# UARTRecoder.net
KiCad netlist of a schematic drawn in Altium Designer
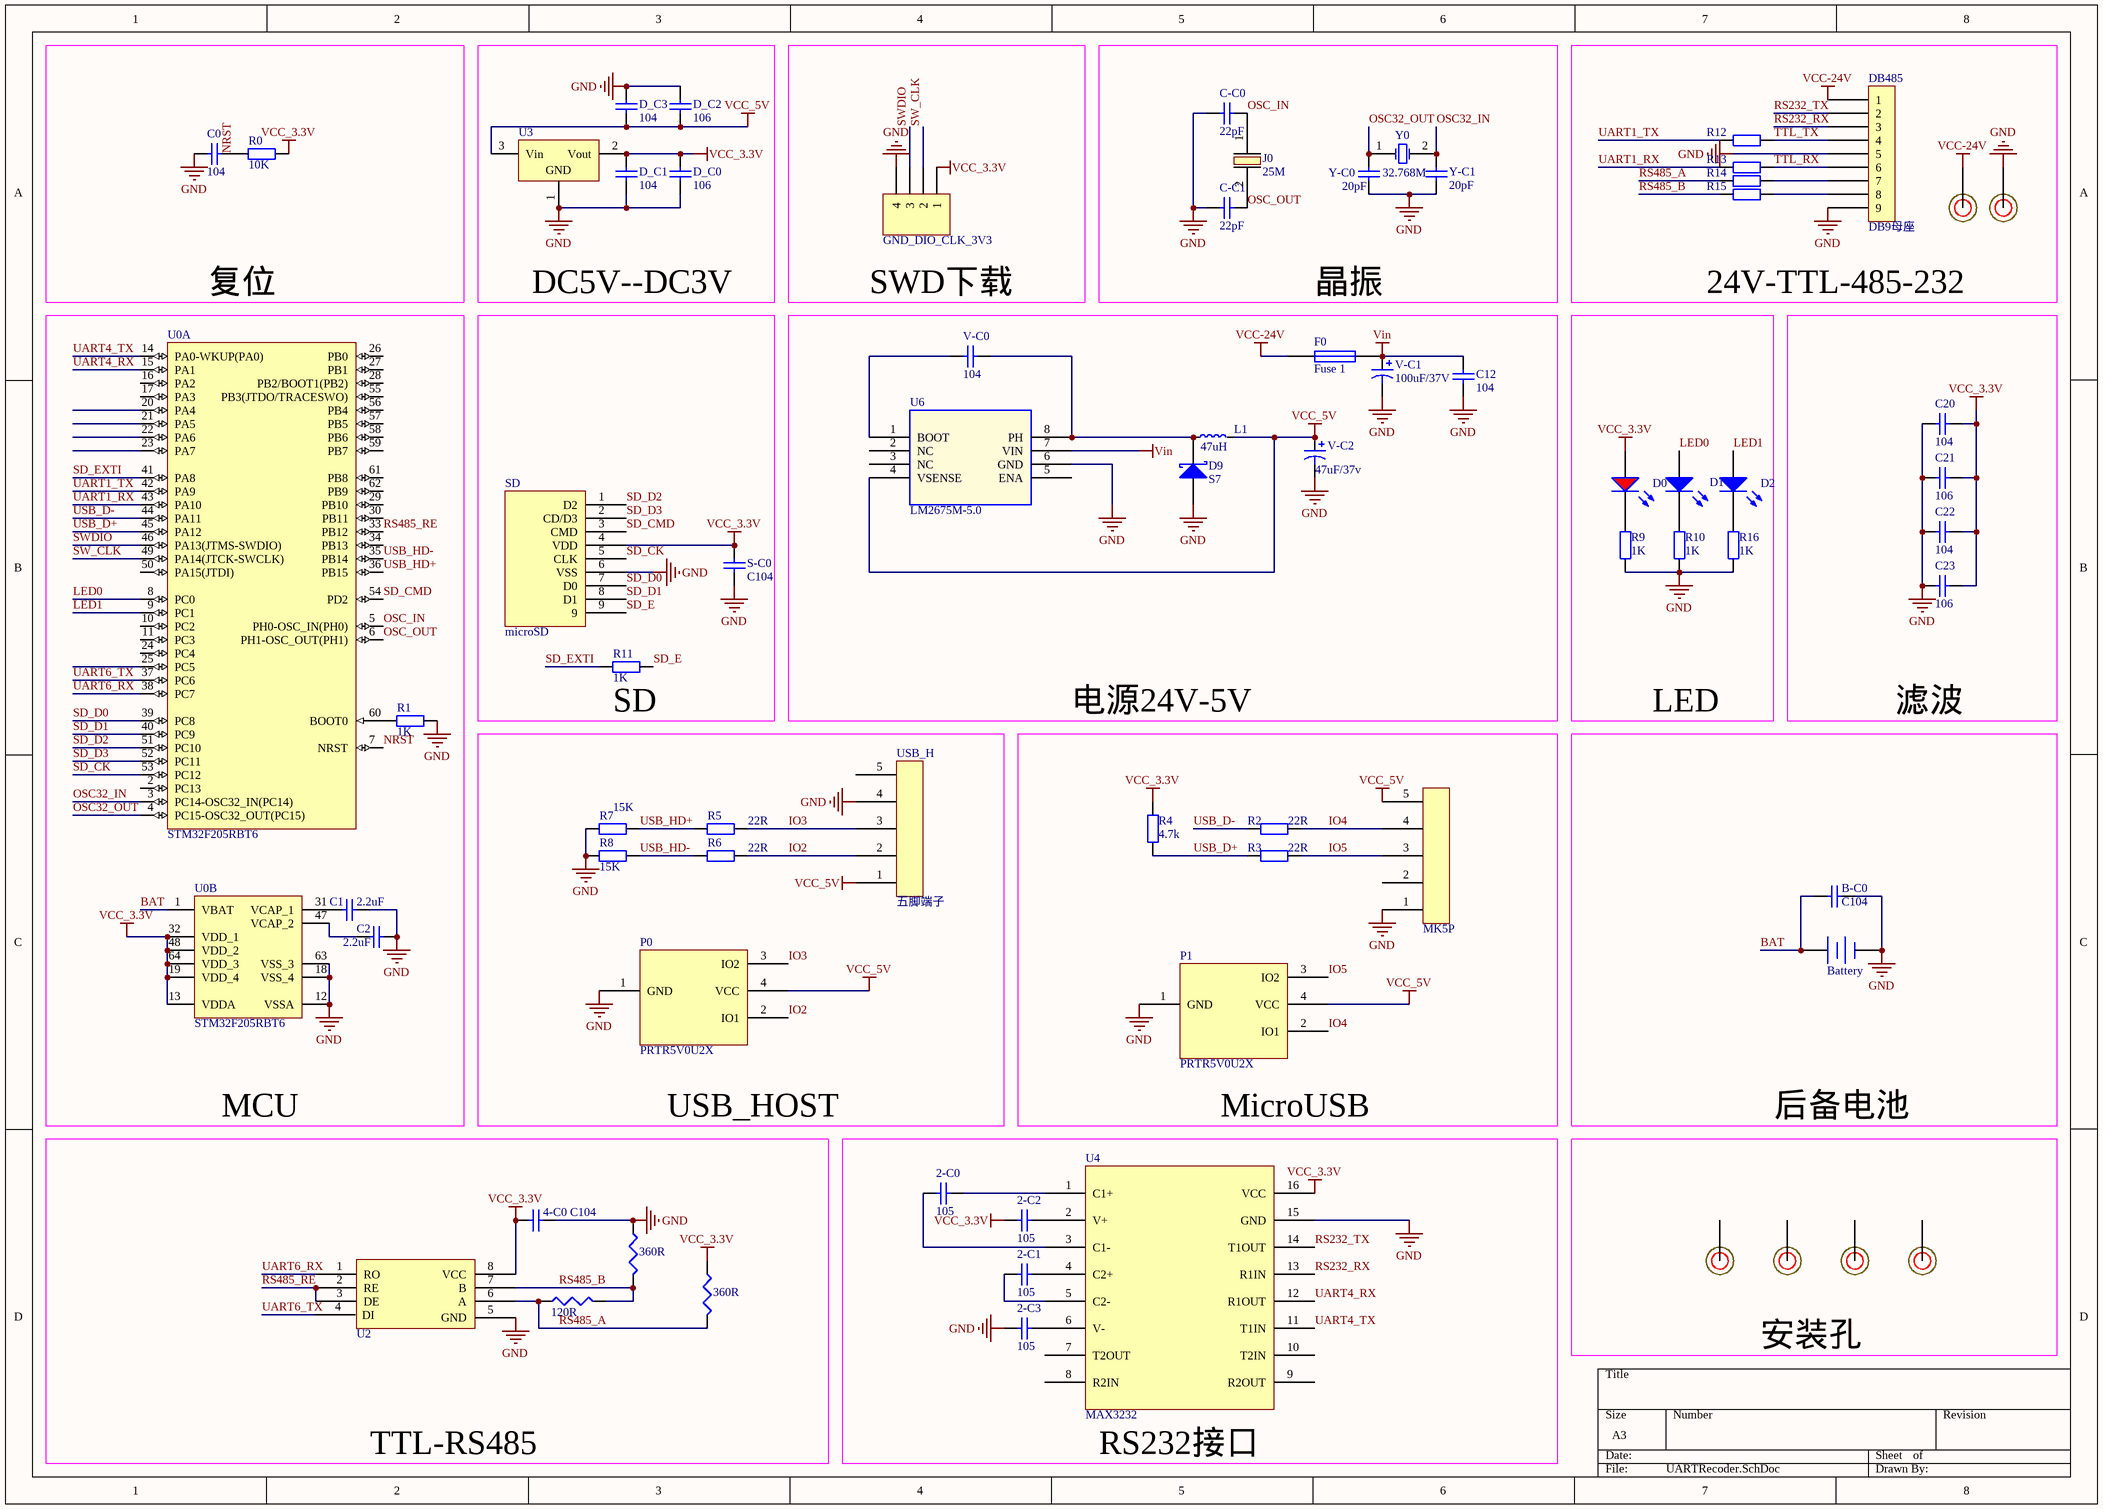
[diagram p0: UARTRecoder.SchDoc]

(export (version "E")
  (design (tool "Eeschema 10.0.6"))
  (components
    (comp (ref "2-C0")
      (value "105")
      (footprint "C-RAD-0805")
      (description "贴片电容")
      (libsource (lib "JiaLiChuang") (part "0805 1uF (105) 10% 50V"))
    )
    (comp (ref "2-C1")
      (value "105")
      (footprint "C-RAD-0805")
      (description "贴片电容")
      (libsource (lib "JiaLiChuang") (part "0805 1uF (105) 10% 50V"))
    )
    (comp (ref "2-C2")
      (value "105")
      (footprint "C-RAD-0805")
      (description "贴片电容")
      (libsource (lib "JiaLiChuang") (part "0805 1uF (105) 10% 50V"))
    )
    (comp (ref "2-C3")
      (value "105")
      (footprint "C-RAD-0805")
      (description "贴片电容")
      (libsource (lib "JiaLiChuang") (part "0805 1uF (105) 10% 50V"))
    )
    (comp (ref "4-C0")
      (value "C104")
      (footprint "C-RAD-0805")
      (description "Capacitor (Semiconductor SIM Model)")
      (fields (field (name "PUBLISHER") "Altium Limited"))
      (libsource (lib "Miscellaneous Devices") (part "Cap Semi"))
    )
    (comp (ref "4-R0")
      (value "360R")
      (footprint "R2012-0805")
      (description "Resistor")
      (fields (field (name "Comment") "R360"))
      (libsource (lib "Miscellaneous Devices") (part "Res3"))
    )
    (comp (ref "4-R1")
      (value "360R")
      (footprint "R2012-0805")
      (description "Resistor")
      (fields (field (name "Comment") "R360"))
      (libsource (lib "Miscellaneous Devices") (part "Res3"))
    )
    (comp (ref "4-R2")
      (value "120R")
      (footprint "R2012-0805")
      (description "Resistor")
      (fields (field (name "Comment") "R120"))
      (libsource (lib "Miscellaneous Devices") (part "Res3"))
    )
    (comp (ref "24V") (value "1孔") (footprint "HOLEx1") (libsource (lib "我的库") (part "1孔")))
    (comp (ref "B-C0")
      (value "C104")
      (footprint "C-RAD-0805")
      (description "Capacitor (Semiconductor SIM Model)")
      (fields (field (name "PUBLISHER") "Altium Limited"))
      (libsource (lib "Miscellaneous Devices") (part "Cap Semi"))
    )
    (comp (ref "bat")
      (value "Battery")
      (footprint "BATM")
      (description "Multicell Battery")
      (fields (field (name "PUBLISHER") "Altium Limited"))
      (libsource (lib "Devices") (part "Battery"))
    )
    (comp (ref "C-C0")
      (value "22pF")
      (footprint "C-RAD-0805")
      (description "贴片电容")
      (libsource (lib "Miscellaneous Devices LC") (part "0603 22pF (220) 5% 50V"))
    )
    (comp (ref "C-C1")
      (value "22pF")
      (footprint "C-RAD-0805")
      (description "贴片电容")
      (libsource (lib "Miscellaneous Devices LC") (part "0603 22pF (220) 5% 50V"))
    )
    (comp (ref "C0")
      (value "104")
      (footprint "C-RAD-0805")
      (description "贴片电容")
      (libsource (lib "JiaLiChuang") (part "0805 100nF(104) 10% 50V"))
    )
    (comp (ref "C1")
      (value "2.2uF")
      (footprint "C-RAD-0805")
      (description "贴片电容")
      (libsource (lib "JiaLiChuang") (part "0805 2.2uF (225) 20% 50V"))
    )
    (comp (ref "C2")
      (value "2.2uF")
      (footprint "C-RAD-0805")
      (description "贴片电容")
      (libsource (lib "JiaLiChuang") (part "0805 2.2uF (225) 20% 50V"))
    )
    (comp (ref "C12")
      (value "104")
      (footprint "C-RAD-0805")
      (description "Capacitor")
      (fields (field (name "PUBLISHER") "Altium Limited"))
      (libsource (lib "*") (part "Cap"))
    )
    (comp (ref "C20")
      (value "104")
      (footprint "C-RAD-0805")
      (description "Capacitor")
      (fields (field (name "PUBLISHER") "Altium Limited"))
      (libsource (lib "*") (part "Cap"))
    )
    (comp (ref "C21")
      (value "106")
      (footprint "C-RAD-0805")
      (description "Capacitor")
      (fields (field (name "PUBLISHER") "Altium Limited"))
      (libsource (lib "*") (part "Cap"))
    )
    (comp (ref "C22")
      (value "104")
      (footprint "C-RAD-0805")
      (description "Capacitor")
      (fields (field (name "PUBLISHER") "Altium Limited"))
      (libsource (lib "*") (part "Cap"))
    )
    (comp (ref "C23")
      (value "106")
      (footprint "C-RAD-0805")
      (description "Capacitor")
      (fields (field (name "PUBLISHER") "Altium Limited"))
      (libsource (lib "*") (part "Cap"))
    )
    (comp (ref "D0")
      (value "Rled")
      (footprint "0805_LED_S1")
      (description "发光二极管")
      (libsource (lib "JiaLiChuang") (part "0805 红灯"))
    )
    (comp (ref "D1")
      (value "Bled")
      (footprint "0805_LED_S1")
      (description "发光二极管")
      (libsource (lib "JiaLiChuang") (part "0805 蓝灯"))
    )
    (comp (ref "D2")
      (value "Bled")
      (footprint "0805_LED_S1")
      (description "发光二极管")
      (libsource (lib "JiaLiChuang") (part "0805 蓝灯"))
    )
    (comp (ref "D9")
      (value "S7")
      (footprint "SOD123")
      (description "Schottky Diode")
      (fields (field (name "PUBLISHER") "Altium Limited"))
      (libsource (lib "*") (part "D Schottky"))
    )
    (comp (ref "DB485") (value "DB9母座") (footprint "DB9-F") (libsource (lib "我的库") (part "9脚封装DB9")))
    (comp (ref "D_C0")
      (value "106")
      (footprint "C-RAD-0805")
      (description "贴片电容")
      (libsource (lib "JiaLiChuang") (part "0805 100nF(104) 10% 50V"))
    )
    (comp (ref "D_C1")
      (value "104")
      (footprint "C-RAD-0805")
      (description "贴片电容")
      (libsource (lib "JiaLiChuang") (part "0805 100nF(104) 10% 50V"))
    )
    (comp (ref "D_C2")
      (value "106")
      (footprint "C-RAD-0805")
      (description "贴片电容")
      (libsource (lib "JiaLiChuang") (part "0805 100nF(104) 10% 50V"))
    )
    (comp (ref "D_C3")
      (value "104")
      (footprint "C-RAD-0805")
      (description "贴片电容")
      (libsource (lib "JiaLiChuang") (part "0805 100nF(104) 10% 50V"))
    )
    (comp (ref "EGND0") (value "1孔") (footprint "HOLEx1") (libsource (lib "我的库") (part "1孔")))
    (comp (ref "EGND1") (value "1孔") (footprint "HOLEx1") (libsource (lib "我的库") (part "1孔")))
    (comp (ref "EGND2") (value "1孔") (footprint "HOLEx1") (libsource (lib "我的库") (part "1孔")))
    (comp (ref "EGND3") (value "1孔") (footprint "HOLEx1") (libsource (lib "我的库") (part "1孔")))
    (comp (ref "F0")
      (value "Fuse 1")
      (footprint "1812")
      (description "Fuse")
      (fields (field (name "PUBLISHER") "Altium Limited"))
      (libsource (lib "Devices") (part "Fuse 1"))
    )
    (comp (ref "GND") (value "1孔") (footprint "HOLEx1") (libsource (lib "我的库") (part "1孔")))
    (comp (ref "GND_DIO_CLK_3V3")
      (value "Header 4")
      (footprint "HDR1X4")
      (description "Header, 4-Pin")
      (fields (field (name "PUBLISHER") "Altium Limited"))
      (libsource (lib "Connectors") (part "Header 4"))
    )
    (comp (ref "J0") (value "25M") (footprint "晶振HC-49S") (libsource (lib "MyADLib") (part "晶振")))
    (comp (ref "L1") (value "47uH") (footprint "L-SMD-7") (libsource (lib "*") (part "Lnductor")))
    (comp (ref "MK5P") (value "五脚端子") (footprint "USB-MICRO1") (libsource (lib "我的库") (part "五脚端子")))
    (comp (ref "P0") (value "PRTR5V0U2X") (footprint "SOT-143") (libsource (lib "我的库") (part "PRTR5V0U2X")))
    (comp (ref "P1") (value "PRTR5V0U2X") (footprint "SOT-143") (libsource (lib "我的库") (part "PRTR5V0U2X")))
    (comp (ref "R0")
      (value "10K")
      (footprint "R2012-0805")
      (description "贴片电阻")
      (libsource (lib "JiaLiChuang") (part "0805 1KΩ (1001) 1%"))
    )
    (comp (ref "R1")
      (value "1K")
      (footprint "R2012-0805")
      (description "贴片电阻")
      (libsource (lib "JiaLiChuang") (part "0603 1KΩ (1001) 1%"))
    )
    (comp (ref "R2")
      (value "22R")
      (footprint "R2012-0805")
      (description "贴片电阻")
      (libsource (lib "") (part "0805 1KΩ (1001) 1%_2"))
    )
    (comp (ref "R3")
      (value "22R")
      (footprint "R2012-0805")
      (description "贴片电阻")
      (libsource (lib "") (part "0805 1KΩ (1001) 1%_2"))
    )
    (comp (ref "R4")
      (value "4.7k")
      (footprint "R2012-0805")
      (description "贴片电阻")
      (libsource (lib "") (part "0805 1KΩ (1001) 1%_1"))
    )
    (comp (ref "R5")
      (value "22R")
      (footprint "R2012-0805")
      (description "贴片电阻")
      (libsource (lib "") (part "0805 1KΩ (1001) 1%_2"))
    )
    (comp (ref "R6")
      (value "22R")
      (footprint "R2012-0805")
      (description "贴片电阻")
      (libsource (lib "") (part "0805 1KΩ (1001) 1%_2"))
    )
    (comp (ref "R7")
      (value "15K")
      (footprint "R2012-0805")
      (description "贴片电阻")
      (libsource (lib "JiaLiChuang") (part "0805 1KΩ (1001) 1%"))
    )
    (comp (ref "R8")
      (value "15K")
      (footprint "R2012-0805")
      (description "贴片电阻")
      (libsource (lib "JiaLiChuang") (part "0805 1KΩ (1001) 1%"))
    )
    (comp (ref "R9")
      (value "1K")
      (footprint "R2012-0805")
      (description "贴片电阻")
      (libsource (lib "") (part "0805 1KΩ (1001) 1%_1"))
    )
    (comp (ref "R10")
      (value "1K")
      (footprint "R2012-0805")
      (description "贴片电阻")
      (libsource (lib "") (part "0805 1KΩ (1001) 1%_1"))
    )
    (comp (ref "R11")
      (value "1K")
      (footprint "R2012-0805")
      (description "贴片电阻")
      (libsource (lib "JiaLiChuang") (part "0603 1KΩ (1001) 1%"))
    )
    (comp (ref "R12")
      (value "1K")
      (footprint "R2012-0805")
      (description "贴片电阻")
      (libsource (lib "JiaLiChuang") (part "0805 1KΩ (1001) 1%"))
    )
    (comp (ref "R13")
      (value "1K")
      (footprint "R2012-0805")
      (description "贴片电阻")
      (libsource (lib "JiaLiChuang") (part "0805 1KΩ (1001) 1%"))
    )
    (comp (ref "R14")
      (value "1K")
      (footprint "R2012-0805")
      (description "贴片电阻")
      (libsource (lib "JiaLiChuang") (part "0805 1KΩ (1001) 1%"))
    )
    (comp (ref "R15")
      (value "1K")
      (footprint "R2012-0805")
      (description "贴片电阻")
      (libsource (lib "JiaLiChuang") (part "0805 1KΩ (1001) 1%"))
    )
    (comp (ref "R16")
      (value "1K")
      (footprint "R2012-0805")
      (description "贴片电阻")
      (libsource (lib "") (part "0805 1KΩ (1001) 1%_1"))
    )
    (comp (ref "S-C0")
      (value "C104")
      (footprint "C-RAD-0805")
      (description "Capacitor (Semiconductor SIM Model)")
      (fields (field (name "PUBLISHER") "Altium Limited"))
      (libsource (lib "Miscellaneous Devices") (part "Cap Semi"))
    )
    (comp (ref "SD") (value "microSD") (footprint "SDCARD_B") (libsource (lib "我的库") (part "microSD")))
    (comp (ref "U0")
      (value "STM32F205RBT6")
      (footprint "LQFP-64")
      (libsource (lib "STM32F2") (part "STM32F205RBT6"))
    )
    (comp (ref "U2") (value "485") (footprint "SOP8") (libsource (lib "我的库") (part "SP3485")))
    (comp (ref "U3")
      (value "AMS1117-3.3")
      (footprint "SOT-223")
      (description "低压差线性稳压(LDO)")
      (libsource (lib "JiaLiChuang") (part "SOT-223 AMS1117-3.3"))
    )
    (comp (ref "U4") (value "MAX3232") (footprint "SOP-16") (libsource (lib "我的库") (part "MAX3232")))
    (comp (ref "U6")
      (value "LM2675M-5.0")
      (footprint "SOP8 - 3d")
      (libsource (lib "Schlib1") (part "TPS5410"))
    )
    (comp (ref "USB_H") (value "五脚端子") (footprint "USB") (libsource (lib "MyADLib") (part "五脚端子")))
    (comp (ref "V-C0")
      (value "104")
      (footprint "C-RAD-0805")
      (description "贴片电容")
      (libsource (lib "JiaLiChuang") (part "0805 100nF(104) 10% 50V"))
    )
    (comp (ref "V-C1")
      (value "100uF/37V")
      (footprint "SMD-EC-F6.3")
      (description "Polarized Capacitor (Surface Mount)")
      (fields (field (name "PUBLISHER") "Altium Limited"))
      (libsource (lib "Miscellaneous Devices") (part "Cap Pol3"))
    )
    (comp (ref "V-C2")
      (value "47uF/37v")
      (footprint "SMD-EC-F4")
      (description "Polarized Capacitor (Surface Mount)")
      (fields (field (name "PUBLISHER") "Altium Limited"))
      (libsource (lib "Miscellaneous Devices") (part "Cap Pol3"))
    )
    (comp (ref "Y-C0")
      (value "20pF")
      (footprint "C-RAD-0805")
      (description "贴片电容")
      (libsource (lib "Miscellaneous Devices LC") (part "0805 20pF (200) 5% 50V"))
    )
    (comp (ref "Y-C1")
      (value "20pF")
      (footprint "C-RAD-0805")
      (description "贴片电容")
      (libsource (lib "Miscellaneous Devices LC") (part "0805 20pF (200) 5% 50V"))
    )
    (comp (ref "Y0")
      (value "32.768M")
      (footprint "XTAL32")
      (description "Crystal Oscillator")
      (fields (field (name "PUBLISHER") "Altium Limited"))
      (libsource (lib "Miscellaneous Devices") (part "XTAL"))
    )
  )
  (nets
    (net (code "1") (name "/BAT") (class "Default")
      (node (ref "B-C0") (pin "2") (pinfunction "2_2") (pintype "passive"))
      (node (ref "U0") (pin "1") (pinfunction "VBAT_1") (pintype "power_in"))
      (node (ref "bat") (pin "1") (pinfunction "+_1") (pintype "passive"))
    )
    (net (code "2") (name "/IO2") (class "Default")
      (node (ref "P0") (pin "2") (pinfunction "IO1_2") (pintype "passive"))
      (node (ref "R6") (pin "2") (pinfunction "2_2") (pintype "passive"))
      (node (ref "USB_H") (pin "2") (pinfunction "2_2") (pintype "passive"))
    )
    (net (code "3") (name "/IO3") (class "Default")
      (node (ref "P0") (pin "3") (pinfunction "IO2_3") (pintype "passive"))
      (node (ref "R5") (pin "2") (pinfunction "2_2") (pintype "passive"))
      (node (ref "USB_H") (pin "3") (pinfunction "3_3") (pintype "passive"))
    )
    (net (code "4") (name "/IO4") (class "Default")
      (node (ref "MK5P") (pin "4") (pinfunction "4_4") (pintype "passive"))
      (node (ref "P1") (pin "2") (pinfunction "IO1_2") (pintype "passive"))
      (node (ref "R2") (pin "2") (pinfunction "2_2") (pintype "passive"))
    )
    (net (code "5") (name "/IO5") (class "Default")
      (node (ref "MK5P") (pin "3") (pinfunction "3_3") (pintype "passive"))
      (node (ref "P1") (pin "3") (pinfunction "IO2_3") (pintype "passive"))
      (node (ref "R3") (pin "2") (pinfunction "2_2") (pintype "passive"))
    )
    (net (code "6") (name "/LED0") (class "Default")
      (node (ref "D1") (pin "A") (pinfunction "A_A") (pintype "passive"))
      (node (ref "U0") (pin "8") (pinfunction "PC0_8") (pintype "bidirectional"))
    )
    (net (code "7") (name "/LED1") (class "Default")
      (node (ref "D2") (pin "A") (pinfunction "A_A") (pintype "passive"))
      (node (ref "U0") (pin "9") (pinfunction "PC1_9") (pintype "bidirectional"))
    )
    (net (code "8") (name "/NRST") (class "Default")
      (node (ref "C0") (pin "1") (pinfunction "1_1") (pintype "passive"))
      (node (ref "R0") (pin "2") (pinfunction "2_2") (pintype "passive"))
      (node (ref "U0") (pin "7") (pinfunction "NRST_7") (pintype "bidirectional"))
    )
    (net (code "9") (name "/OSC32_IN") (class "Default")
      (node (ref "U0") (pin "3") (pinfunction "PC14-OSC32_IN(PC14)_3") (pintype "bidirectional"))
      (node (ref "Y-C1") (pin "2") (pinfunction "2_2") (pintype "passive"))
      (node (ref "Y0") (pin "2") (pinfunction "OSC2_2") (pintype "passive"))
    )
    (net (code "10") (name "/OSC32_OUT") (class "Default")
      (node (ref "U0") (pin "4") (pinfunction "PC15-OSC32_OUT(PC15)_4") (pintype "bidirectional"))
      (node (ref "Y-C0") (pin "2") (pinfunction "2_2") (pintype "passive"))
      (node (ref "Y0") (pin "1") (pinfunction "OSC1_1") (pintype "passive"))
    )
    (net (code "11") (name "/OSC_IN") (class "Default")
      (node (ref "C-C0") (pin "2") (pinfunction "2_2") (pintype "passive"))
      (node (ref "J0") (pin "1") (pinfunction "1_1") (pintype "passive"))
      (node (ref "U0") (pin "5") (pinfunction "PH0-OSC_IN(PH0)_5") (pintype "bidirectional"))
    )
    (net (code "12") (name "/OSC_OUT") (class "Default")
      (node (ref "C-C1") (pin "2") (pinfunction "2_2") (pintype "passive"))
      (node (ref "J0") (pin "2") (pinfunction "2_2") (pintype "passive"))
      (node (ref "U0") (pin "6") (pinfunction "PH1-OSC_OUT(PH1)_6") (pintype "bidirectional"))
    )
    (net (code "13") (name "/RS232_RX") (class "Default")
      (node (ref "DB485") (pin "3") (pinfunction "3_3") (pintype "passive"))
      (node (ref "U4") (pin "13") (pinfunction "R1IN_13") (pintype "passive"))
    )
    (net (code "14") (name "/RS232_TX") (class "Default")
      (node (ref "DB485") (pin "2") (pinfunction "2_2") (pintype "passive"))
      (node (ref "U4") (pin "14") (pinfunction "T1OUT_14") (pintype "passive"))
    )
    (net (code "15") (name "/RS485_A") (class "Default")
      (node (ref "4-R0") (pin "2") (pinfunction "2_2") (pintype "passive"))
      (node (ref "4-R2") (pin "1") (pinfunction "1_1") (pintype "passive"))
      (node (ref "R14") (pin "2") (pinfunction "2_2") (pintype "passive"))
      (node (ref "U2") (pin "6") (pinfunction "A_6") (pintype "passive"))
    )
    (net (code "16") (name "/RS485_B") (class "Default")
      (node (ref "4-R1") (pin "2") (pinfunction "2_2") (pintype "passive"))
      (node (ref "4-R2") (pin "2") (pinfunction "2_2") (pintype "passive"))
      (node (ref "R15") (pin "2") (pinfunction "2_2") (pintype "passive"))
      (node (ref "U2") (pin "7") (pinfunction "B_7") (pintype "passive"))
    )
    (net (code "17") (name "/RS485_RE") (class "Default")
      (node (ref "U0") (pin "33") (pinfunction "PB12_33") (pintype "bidirectional"))
      (node (ref "U2") (pin "2") (pinfunction "RE_2") (pintype "passive"))
      (node (ref "U2") (pin "3") (pinfunction "DE_3") (pintype "passive"))
    )
    (net (code "18") (name "/SD_CK") (class "Default")
      (node (ref "SD") (pin "5") (pinfunction "CLK_5") (pintype "passive"))
      (node (ref "U0") (pin "53") (pinfunction "PC12_53") (pintype "bidirectional"))
    )
    (net (code "19") (name "/SD_CMD") (class "Default")
      (node (ref "SD") (pin "3") (pinfunction "CMD_3") (pintype "passive"))
      (node (ref "U0") (pin "54") (pinfunction "PD2_54") (pintype "bidirectional"))
    )
    (net (code "20") (name "/SD_D0") (class "Default")
      (node (ref "SD") (pin "7") (pinfunction "D0_7") (pintype "passive"))
      (node (ref "U0") (pin "39") (pinfunction "PC8_39") (pintype "bidirectional"))
    )
    (net (code "21") (name "/SD_D1") (class "Default")
      (node (ref "SD") (pin "8") (pinfunction "D1_8") (pintype "passive"))
      (node (ref "U0") (pin "40") (pinfunction "PC9_40") (pintype "bidirectional"))
    )
    (net (code "22") (name "/SD_D2") (class "Default")
      (node (ref "SD") (pin "1") (pinfunction "D2_1") (pintype "passive"))
      (node (ref "U0") (pin "51") (pinfunction "PC10_51") (pintype "bidirectional"))
    )
    (net (code "23") (name "/SD_D3") (class "Default")
      (node (ref "SD") (pin "2") (pinfunction "CD/D3_2") (pintype "passive"))
      (node (ref "U0") (pin "52") (pinfunction "PC11_52") (pintype "bidirectional"))
    )
    (net (code "24") (name "/SD_E") (class "Default")
      (node (ref "R11") (pin "2") (pinfunction "2_2") (pintype "passive"))
      (node (ref "SD") (pin "9") (pinfunction "9_9") (pintype "passive"))
    )
    (net (code "25") (name "/SD_EXTI") (class "Default")
      (node (ref "R11") (pin "1") (pinfunction "1_1") (pintype "passive"))
      (node (ref "U0") (pin "41") (pinfunction "PA8_41") (pintype "bidirectional"))
    )
    (net (code "26") (name "/SWDIO") (class "Default")
      (node (ref "GND_DIO_CLK_3V3") (pin "3") (pinfunction "3_3") (pintype "passive"))
      (node (ref "U0") (pin "46") (pinfunction "PA13(JTMS-SWDIO)_46") (pintype "bidirectional"))
    )
    (net (code "27") (name "/SW_CLK") (class "Default")
      (node (ref "GND_DIO_CLK_3V3") (pin "2") (pinfunction "2_2") (pintype "passive"))
      (node (ref "U0") (pin "49") (pinfunction "PA14(JTCK-SWCLK)_49") (pintype "bidirectional"))
    )
    (net (code "28") (name "/TTL_RX") (class "Default")
      (node (ref "DB485") (pin "6") (pinfunction "6_6") (pintype "passive"))
      (node (ref "R13") (pin "1") (pinfunction "1_1") (pintype "passive"))
    )
    (net (code "29") (name "/TTL_TX") (class "Default")
      (node (ref "DB485") (pin "4") (pinfunction "4_4") (pintype "passive"))
      (node (ref "R12") (pin "1") (pinfunction "1_1") (pintype "passive"))
    )
    (net (code "30") (name "/UART1_RX") (class "Default")
      (node (ref "R13") (pin "2") (pinfunction "2_2") (pintype "passive"))
      (node (ref "U0") (pin "43") (pinfunction "PA10_43") (pintype "bidirectional"))
    )
    (net (code "31") (name "/UART1_TX") (class "Default")
      (node (ref "R12") (pin "2") (pinfunction "2_2") (pintype "passive"))
      (node (ref "U0") (pin "42") (pinfunction "PA9_42") (pintype "bidirectional"))
    )
    (net (code "32") (name "/UART4_RX") (class "Default")
      (node (ref "U0") (pin "15") (pinfunction "PA1_15") (pintype "bidirectional"))
      (node (ref "U4") (pin "12") (pinfunction "R1OUT_12") (pintype "passive"))
    )
    (net (code "33") (name "/UART4_TX") (class "Default")
      (node (ref "U0") (pin "14") (pinfunction "PA0-WKUP(PA0)_14") (pintype "bidirectional"))
      (node (ref "U4") (pin "11") (pinfunction "T1IN_11") (pintype "passive"))
    )
    (net (code "34") (name "/UART6_RX") (class "Default")
      (node (ref "U0") (pin "38") (pinfunction "PC7_38") (pintype "bidirectional"))
      (node (ref "U2") (pin "1") (pinfunction "RO_1") (pintype "passive"))
    )
    (net (code "35") (name "/UART6_TX") (class "Default")
      (node (ref "U0") (pin "37") (pinfunction "PC6_37") (pintype "bidirectional"))
      (node (ref "U2") (pin "4") (pinfunction "DI_4") (pintype "passive"))
    )
    (net (code "36") (name "/USB_D+") (class "Default")
      (node (ref "R3") (pin "1") (pinfunction "1_1") (pintype "passive"))
      (node (ref "R4") (pin "1") (pinfunction "1_1") (pintype "passive"))
      (node (ref "U0") (pin "45") (pinfunction "PA12_45") (pintype "bidirectional"))
    )
    (net (code "37") (name "/USB_D-") (class "Default")
      (node (ref "R2") (pin "1") (pinfunction "1_1") (pintype "passive"))
      (node (ref "U0") (pin "44") (pinfunction "PA11_44") (pintype "bidirectional"))
    )
    (net (code "38") (name "/USB_HD+") (class "Default")
      (node (ref "R5") (pin "1") (pinfunction "1_1") (pintype "passive"))
      (node (ref "R7") (pin "1") (pinfunction "1_1") (pintype "passive"))
      (node (ref "U0") (pin "36") (pinfunction "PB15_36") (pintype "bidirectional"))
    )
    (net (code "39") (name "/USB_HD-") (class "Default")
      (node (ref "R6") (pin "1") (pinfunction "1_1") (pintype "passive"))
      (node (ref "R8") (pin "1") (pinfunction "1_1") (pintype "passive"))
      (node (ref "U0") (pin "35") (pinfunction "PB14_35") (pintype "bidirectional"))
    )
    (net (code "40") (name "GND") (class "Default")
      (node (ref "2-C3") (pin "1") (pinfunction "1_1") (pintype "passive"))
      (node (ref "4-C0") (pin "1") (pinfunction "1_1") (pintype "passive"))
      (node (ref "4-R1") (pin "1") (pinfunction "1_1") (pintype "passive"))
      (node (ref "B-C0") (pin "1") (pinfunction "1_1") (pintype "passive"))
      (node (ref "C-C0") (pin "1") (pinfunction "1_1") (pintype "passive"))
      (node (ref "C-C1") (pin "1") (pinfunction "1_1") (pintype "passive"))
      (node (ref "C0") (pin "2") (pinfunction "2_2") (pintype "passive"))
      (node (ref "C1") (pin "2") (pinfunction "2_2") (pintype "passive"))
      (node (ref "C12") (pin "2") (pinfunction "2_2") (pintype "passive"))
      (node (ref "C2") (pin "2") (pinfunction "2_2") (pintype "passive"))
      (node (ref "C20") (pin "1") (pinfunction "1_1") (pintype "passive"))
      (node (ref "C21") (pin "1") (pinfunction "1_1") (pintype "passive"))
      (node (ref "C22") (pin "1") (pinfunction "1_1") (pintype "passive"))
      (node (ref "C23") (pin "1") (pinfunction "1_1") (pintype "passive"))
      (node (ref "D9") (pin "1") (pinfunction "A_1") (pintype "passive"))
      (node (ref "DB485") (pin "5") (pinfunction "5_5") (pintype "passive"))
      (node (ref "DB485") (pin "9") (pinfunction "9_9") (pintype "passive"))
      (node (ref "D_C0") (pin "1") (pinfunction "1_1") (pintype "passive"))
      (node (ref "D_C1") (pin "1") (pinfunction "1_1") (pintype "passive"))
      (node (ref "D_C2") (pin "2") (pinfunction "2_2") (pintype "passive"))
      (node (ref "D_C3") (pin "2") (pinfunction "2_2") (pintype "passive"))
      (node (ref "GND") (pin "1") (pinfunction "1_1") (pintype "passive"))
      (node (ref "GND_DIO_CLK_3V3") (pin "4") (pinfunction "4_4") (pintype "passive"))
      (node (ref "MK5P") (pin "1") (pinfunction "1_1") (pintype "passive"))
      (node (ref "P0") (pin "1") (pinfunction "GND_1") (pintype "passive"))
      (node (ref "P1") (pin "1") (pinfunction "GND_1") (pintype "passive"))
      (node (ref "R1") (pin "2") (pinfunction "2_2") (pintype "passive"))
      (node (ref "R10") (pin "1") (pinfunction "1_1") (pintype "passive"))
      (node (ref "R16") (pin "1") (pinfunction "1_1") (pintype "passive"))
      (node (ref "R7") (pin "2") (pinfunction "2_2") (pintype "passive"))
      (node (ref "R8") (pin "2") (pinfunction "2_2") (pintype "passive"))
      (node (ref "R9") (pin "1") (pinfunction "1_1") (pintype "passive"))
      (node (ref "S-C0") (pin "2") (pinfunction "2_2") (pintype "passive"))
      (node (ref "SD") (pin "6") (pinfunction "VSS_6") (pintype "passive"))
      (node (ref "U0") (pin "12") (pinfunction "VSSA_12") (pintype "power_in"))
      (node (ref "U0") (pin "18") (pinfunction "VSS_4_18") (pintype "power_in"))
      (node (ref "U0") (pin "63") (pinfunction "VSS_3_63") (pintype "power_in"))
      (node (ref "U2") (pin "5") (pinfunction "GND_5") (pintype "passive"))
      (node (ref "U3") (pin "1") (pinfunction "GND_1") (pintype "passive"))
      (node (ref "U4") (pin "15") (pinfunction "GND_15") (pintype "passive"))
      (node (ref "U6") (pin "6") (pinfunction "GND_6") (pintype "passive"))
      (node (ref "USB_H") (pin "4") (pinfunction "4_4") (pintype "passive"))
      (node (ref "V-C1") (pin "2") (pinfunction "2_2") (pintype "passive"))
      (node (ref "V-C2") (pin "2") (pinfunction "2_2") (pintype "passive"))
      (node (ref "Y-C0") (pin "1") (pinfunction "1_1") (pintype "passive"))
      (node (ref "Y-C1") (pin "1") (pinfunction "1_1") (pintype "passive"))
      (node (ref "bat") (pin "2") (pinfunction "-_2") (pintype "passive"))
    )
    (net (code "41") (name "Net-(D0-PadK)") (class "Default")
      (node (ref "D0") (pin "K") (pinfunction "K_K") (pintype "passive"))
      (node (ref "R9") (pin "2") (pinfunction "2_2") (pintype "passive"))
    )
    (net (code "42") (name "Net-(D1-PadK)") (class "Default")
      (node (ref "D1") (pin "K") (pinfunction "K_K") (pintype "passive"))
      (node (ref "R10") (pin "2") (pinfunction "2_2") (pintype "passive"))
    )
    (net (code "43") (name "Net-(D2-PadK)") (class "Default")
      (node (ref "D2") (pin "K") (pinfunction "K_K") (pintype "passive"))
      (node (ref "R16") (pin "2") (pinfunction "2_2") (pintype "passive"))
    )
    (net (code "44") (name "Net-(D9-K)") (class "Default")
      (node (ref "D9") (pin "2") (pinfunction "K_2") (pintype "passive"))
      (node (ref "L1") (pin "1") (pinfunction "1_1") (pintype "passive"))
      (node (ref "U6") (pin "8") (pinfunction "PH_8") (pintype "passive"))
      (node (ref "V-C0") (pin "2") (pinfunction "2_2") (pintype "passive"))
    )
    (net (code "45") (name "Net-(DB485-Pad7)") (class "Default")
      (node (ref "DB485") (pin "7") (pinfunction "7_7") (pintype "passive"))
      (node (ref "R14") (pin "1") (pinfunction "1_1") (pintype "passive"))
    )
    (net (code "46") (name "Net-(DB485-Pad8)") (class "Default")
      (node (ref "DB485") (pin "8") (pinfunction "8_8") (pintype "passive"))
      (node (ref "R15") (pin "1") (pinfunction "1_1") (pintype "passive"))
    )
    (net (code "47") (name "Net-(U0A-BOOT0)") (class "Default")
      (node (ref "R1") (pin "1") (pinfunction "1_1") (pintype "passive"))
      (node (ref "U0") (pin "60") (pinfunction "BOOT0_60") (pintype "input"))
    )
    (net (code "48") (name "Net-(U0B-VCAP_1)") (class "Default")
      (node (ref "C1") (pin "1") (pinfunction "1_1") (pintype "passive"))
      (node (ref "U0") (pin "31") (pinfunction "VCAP_1_31") (pintype "power_in"))
    )
    (net (code "49") (name "Net-(U0B-VCAP_2)") (class "Default")
      (node (ref "C2") (pin "1") (pinfunction "1_1") (pintype "passive"))
      (node (ref "U0") (pin "47") (pinfunction "VCAP_2_47") (pintype "power_in"))
    )
    (net (code "50") (name "Net-(U4-C1+)") (class "Default")
      (node (ref "2-C0") (pin "2") (pinfunction "2_2") (pintype "passive"))
      (node (ref "U4") (pin "1") (pinfunction "C1+_1") (pintype "passive"))
    )
    (net (code "51") (name "Net-(U4-C1-)") (class "Default")
      (node (ref "2-C0") (pin "1") (pinfunction "1_1") (pintype "passive"))
      (node (ref "U4") (pin "3") (pinfunction "C1-_3") (pintype "passive"))
    )
    (net (code "52") (name "Net-(U4-C2+)") (class "Default")
      (node (ref "2-C1") (pin "2") (pinfunction "2_2") (pintype "passive"))
      (node (ref "U4") (pin "4") (pinfunction "C2+_4") (pintype "passive"))
    )
    (net (code "53") (name "Net-(U4-C2-)") (class "Default")
      (node (ref "2-C1") (pin "1") (pinfunction "1_1") (pintype "passive"))
      (node (ref "U4") (pin "5") (pinfunction "C2-_5") (pintype "passive"))
    )
    (net (code "54") (name "Net-(U4-V+)") (class "Default")
      (node (ref "2-C2") (pin "2") (pinfunction "2_2") (pintype "passive"))
      (node (ref "U4") (pin "2") (pinfunction "V+_2") (pintype "passive"))
    )
    (net (code "55") (name "Net-(U4-V-)") (class "Default")
      (node (ref "2-C3") (pin "2") (pinfunction "2_2") (pintype "passive"))
      (node (ref "U4") (pin "6") (pinfunction "V-_6") (pintype "passive"))
    )
    (net (code "56") (name "Net-(U6-BOOT)") (class "Default")
      (node (ref "U6") (pin "1") (pinfunction "BOOT_1") (pintype "passive"))
      (node (ref "V-C0") (pin "1") (pinfunction "1_1") (pintype "passive"))
    )
    (net (code "57") (name "VCC-24V") (class "Default")
      (node (ref "24V") (pin "1") (pinfunction "1_1") (pintype "passive"))
      (node (ref "DB485") (pin "1") (pinfunction "1_1") (pintype "passive"))
      (node (ref "F0") (pin "1") (pinfunction "1_1") (pintype "passive"))
    )
    (net (code "58") (name "VCC_3.3V") (class "Default")
      (node (ref "2-C2") (pin "1") (pinfunction "1_1") (pintype "passive"))
      (node (ref "4-C0") (pin "2") (pinfunction "2_2") (pintype "passive"))
      (node (ref "4-R0") (pin "1") (pinfunction "1_1") (pintype "passive"))
      (node (ref "C20") (pin "2") (pinfunction "2_2") (pintype "passive"))
      (node (ref "C21") (pin "2") (pinfunction "2_2") (pintype "passive"))
      (node (ref "C22") (pin "2") (pinfunction "2_2") (pintype "passive"))
      (node (ref "C23") (pin "2") (pinfunction "2_2") (pintype "passive"))
      (node (ref "D0") (pin "A") (pinfunction "A_A") (pintype "passive"))
      (node (ref "D_C0") (pin "2") (pinfunction "2_2") (pintype "passive"))
      (node (ref "D_C1") (pin "2") (pinfunction "2_2") (pintype "passive"))
      (node (ref "GND_DIO_CLK_3V3") (pin "1") (pinfunction "1_1") (pintype "passive"))
      (node (ref "R0") (pin "1") (pinfunction "1_1") (pintype "passive"))
      (node (ref "R4") (pin "2") (pinfunction "2_2") (pintype "passive"))
      (node (ref "S-C0") (pin "1") (pinfunction "1_1") (pintype "passive"))
      (node (ref "SD") (pin "4") (pinfunction "VDD_4") (pintype "passive"))
      (node (ref "U0") (pin "13") (pinfunction "VDDA_13") (pintype "power_in"))
      (node (ref "U0") (pin "19") (pinfunction "VDD_4_19") (pintype "power_in"))
      (node (ref "U0") (pin "32") (pinfunction "VDD_1_32") (pintype "power_in"))
      (node (ref "U0") (pin "48") (pinfunction "VDD_2_48") (pintype "power_in"))
      (node (ref "U0") (pin "64") (pinfunction "VDD_3_64") (pintype "power_in"))
      (node (ref "U2") (pin "8") (pinfunction "VCC_8") (pintype "passive"))
      (node (ref "U3") (pin "2") (pinfunction "Vout_2") (pintype "passive"))
      (node (ref "U4") (pin "16") (pinfunction "VCC_16") (pintype "passive"))
    )
    (net (code "59") (name "VCC_5V") (class "Default")
      (node (ref "D_C2") (pin "1") (pinfunction "1_1") (pintype "passive"))
      (node (ref "D_C3") (pin "1") (pinfunction "1_1") (pintype "passive"))
      (node (ref "L1") (pin "2") (pinfunction "2_2") (pintype "passive"))
      (node (ref "MK5P") (pin "5") (pinfunction "5_5") (pintype "passive"))
      (node (ref "P0") (pin "4") (pinfunction "VCC_4") (pintype "passive"))
      (node (ref "P1") (pin "4") (pinfunction "VCC_4") (pintype "passive"))
      (node (ref "U3") (pin "3") (pinfunction "Vin_3") (pintype "passive"))
      (node (ref "U6") (pin "4") (pinfunction "VSENSE_4") (pintype "passive"))
      (node (ref "USB_H") (pin "1") (pinfunction "1_1") (pintype "passive"))
      (node (ref "V-C2") (pin "1") (pinfunction "1_1") (pintype "passive"))
    )
    (net (code "60") (name "Vin") (class "Default")
      (node (ref "C12") (pin "1") (pinfunction "1_1") (pintype "passive"))
      (node (ref "F0") (pin "2") (pinfunction "2_2") (pintype "passive"))
      (node (ref "U6") (pin "7") (pinfunction "VIN_7") (pintype "passive"))
      (node (ref "V-C1") (pin "1") (pinfunction "1_1") (pintype "passive"))
    )
    (net (code "61") (name "unconnected-(EGND0-Pad1)") (class "Default")
      (node (ref "EGND0") (pin "1") (pinfunction "1_1") (pintype "passive"))
    )
    (net (code "62") (name "unconnected-(EGND1-Pad1)") (class "Default")
      (node (ref "EGND1") (pin "1") (pinfunction "1_1") (pintype "passive"))
    )
    (net (code "63") (name "unconnected-(EGND2-Pad1)") (class "Default")
      (node (ref "EGND2") (pin "1") (pinfunction "1_1") (pintype "passive"))
    )
    (net (code "64") (name "unconnected-(EGND3-Pad1)") (class "Default")
      (node (ref "EGND3") (pin "1") (pinfunction "1_1") (pintype "passive"))
    )
    (net (code "65") (name "unconnected-(MK5P-Pad2)") (class "Default")
      (node (ref "MK5P") (pin "2") (pinfunction "2_2") (pintype "passive"))
    )
    (net (code "66") (name "unconnected-(U0A-PA2-Pad16)") (class "Default")
      (node (ref "U0") (pin "16") (pinfunction "PA2_16") (pintype "bidirectional"))
    )
    (net (code "67") (name "unconnected-(U0A-PA3-Pad17)") (class "Default")
      (node (ref "U0") (pin "17") (pinfunction "PA3_17") (pintype "bidirectional"))
    )
    (net (code "68") (name "unconnected-(U0A-PA4-Pad20)") (class "Default")
      (node (ref "U0") (pin "20") (pinfunction "PA4_20") (pintype "bidirectional"))
    )
    (net (code "69") (name "unconnected-(U0A-PA5-Pad21)") (class "Default")
      (node (ref "U0") (pin "21") (pinfunction "PA5_21") (pintype "bidirectional"))
    )
    (net (code "70") (name "unconnected-(U0A-PA6-Pad22)") (class "Default")
      (node (ref "U0") (pin "22") (pinfunction "PA6_22") (pintype "bidirectional"))
    )
    (net (code "71") (name "unconnected-(U0A-PA7-Pad23)") (class "Default")
      (node (ref "U0") (pin "23") (pinfunction "PA7_23") (pintype "bidirectional"))
    )
    (net (code "72") (name "unconnected-(U0A-PA15(JTDI)-Pad50)") (class "Default")
      (node (ref "U0") (pin "50") (pinfunction "PA15(JTDI)_50") (pintype "bidirectional"))
    )
    (net (code "73") (name "unconnected-(U0A-PB0-Pad26)") (class "Default")
      (node (ref "U0") (pin "26") (pinfunction "PB0_26") (pintype "bidirectional"))
    )
    (net (code "74") (name "unconnected-(U0A-PB1-Pad27)") (class "Default")
      (node (ref "U0") (pin "27") (pinfunction "PB1_27") (pintype "bidirectional"))
    )
    (net (code "75") (name "unconnected-(U0A-PB2{slash}BOOT1(PB2)-Pad28)") (class "Default")
      (node (ref "U0") (pin "28") (pinfunction "PB2/BOOT1(PB2)_28") (pintype "bidirectional"))
    )
    (net (code "76") (name "unconnected-(U0A-PB3(JTDO{slash}TRACESWO)-Pad55)") (class "Default")
      (node (ref "U0") (pin "55") (pinfunction "PB3(JTDO/TRACESWO)_55") (pintype "bidirectional"))
    )
    (net (code "77") (name "unconnected-(U0A-PB4-Pad56)") (class "Default")
      (node (ref "U0") (pin "56") (pinfunction "PB4_56") (pintype "bidirectional"))
    )
    (net (code "78") (name "unconnected-(U0A-PB5-Pad57)") (class "Default")
      (node (ref "U0") (pin "57") (pinfunction "PB5_57") (pintype "bidirectional"))
    )
    (net (code "79") (name "unconnected-(U0A-PB6-Pad58)") (class "Default")
      (node (ref "U0") (pin "58") (pinfunction "PB6_58") (pintype "bidirectional"))
    )
    (net (code "80") (name "unconnected-(U0A-PB7-Pad59)") (class "Default")
      (node (ref "U0") (pin "59") (pinfunction "PB7_59") (pintype "bidirectional"))
    )
    (net (code "81") (name "unconnected-(U0A-PB8-Pad61)") (class "Default")
      (node (ref "U0") (pin "61") (pinfunction "PB8_61") (pintype "bidirectional"))
    )
    (net (code "82") (name "unconnected-(U0A-PB9-Pad62)") (class "Default")
      (node (ref "U0") (pin "62") (pinfunction "PB9_62") (pintype "bidirectional"))
    )
    (net (code "83") (name "unconnected-(U0A-PB10-Pad29)") (class "Default")
      (node (ref "U0") (pin "29") (pinfunction "PB10_29") (pintype "bidirectional"))
    )
    (net (code "84") (name "unconnected-(U0A-PB11-Pad30)") (class "Default")
      (node (ref "U0") (pin "30") (pinfunction "PB11_30") (pintype "bidirectional"))
    )
    (net (code "85") (name "unconnected-(U0A-PB13-Pad34)") (class "Default")
      (node (ref "U0") (pin "34") (pinfunction "PB13_34") (pintype "bidirectional"))
    )
    (net (code "86") (name "unconnected-(U0A-PC2-Pad10)") (class "Default")
      (node (ref "U0") (pin "10") (pinfunction "PC2_10") (pintype "bidirectional"))
    )
    (net (code "87") (name "unconnected-(U0A-PC3-Pad11)") (class "Default")
      (node (ref "U0") (pin "11") (pinfunction "PC3_11") (pintype "bidirectional"))
    )
    (net (code "88") (name "unconnected-(U0A-PC4-Pad24)") (class "Default")
      (node (ref "U0") (pin "24") (pinfunction "PC4_24") (pintype "bidirectional"))
    )
    (net (code "89") (name "unconnected-(U0A-PC5-Pad25)") (class "Default")
      (node (ref "U0") (pin "25") (pinfunction "PC5_25") (pintype "bidirectional"))
    )
    (net (code "90") (name "unconnected-(U0A-PC13-Pad2)") (class "Default")
      (node (ref "U0") (pin "2") (pinfunction "PC13_2") (pintype "bidirectional"))
    )
    (net (code "91") (name "unconnected-(U4-R2IN-Pad8)") (class "Default")
      (node (ref "U4") (pin "8") (pinfunction "R2IN_8") (pintype "passive"))
    )
    (net (code "92") (name "unconnected-(U4-R2OUT-Pad9)") (class "Default")
      (node (ref "U4") (pin "9") (pinfunction "R2OUT_9") (pintype "passive"))
    )
    (net (code "93") (name "unconnected-(U4-T2IN-Pad10)") (class "Default")
      (node (ref "U4") (pin "10") (pinfunction "T2IN_10") (pintype "passive"))
    )
    (net (code "94") (name "unconnected-(U4-T2OUT-Pad7)") (class "Default")
      (node (ref "U4") (pin "7") (pinfunction "T2OUT_7") (pintype "passive"))
    )
    (net (code "95") (name "unconnected-(U6-ENA-Pad5)") (class "Default")
      (node (ref "U6") (pin "5") (pinfunction "ENA_5") (pintype "passive"))
    )
    (net (code "96") (name "unconnected-(U6-NC-Pad2)") (class "Default")
      (node (ref "U6") (pin "2") (pinfunction "NC_2") (pintype "passive"))
    )
    (net (code "97") (name "unconnected-(U6-NC-Pad3)") (class "Default")
      (node (ref "U6") (pin "3") (pinfunction "NC_3") (pintype "passive"))
    )
    (net (code "98") (name "unconnected-(USB_H-Pad5)") (class "Default")
      (node (ref "USB_H") (pin "5") (pinfunction "5_5") (pintype "passive"))
    )
  )
)
